# SCH__Umeko-DEC-H_htpa__2025-03-20_1.net
KiCad netlist of a schematic drawn in EasyEDA
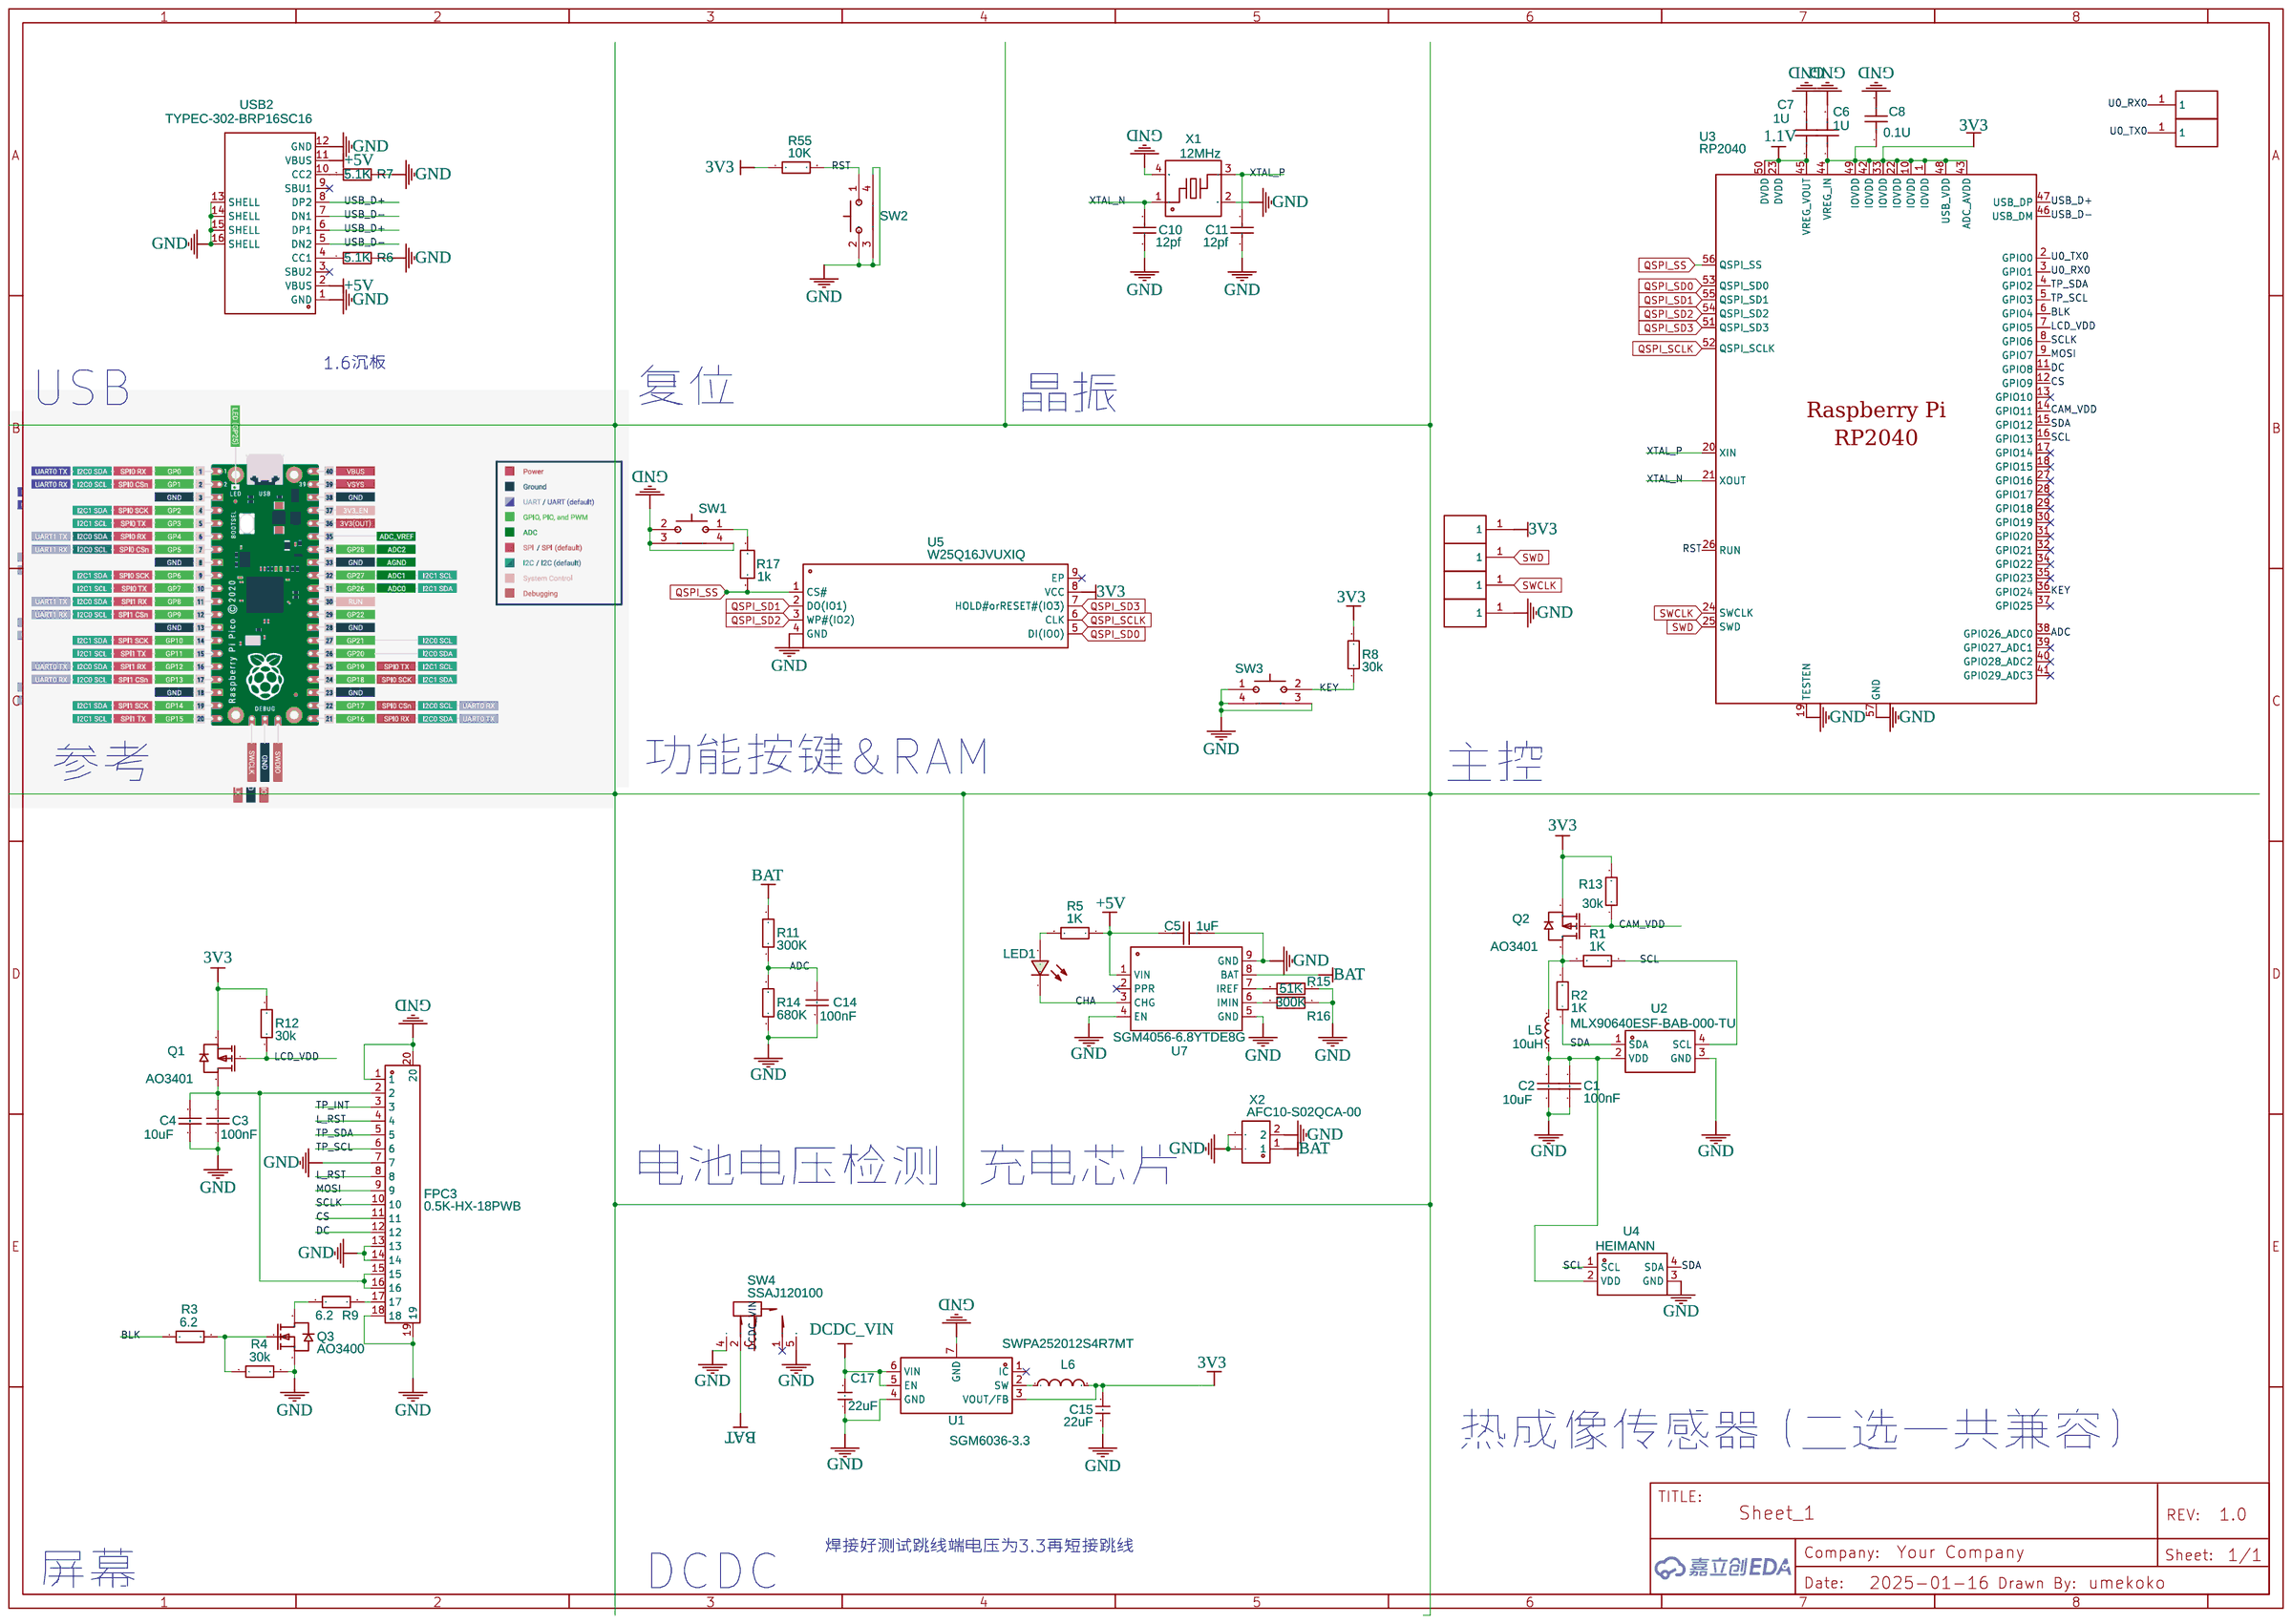
[diagram p0: schematic sheet]

(export (version "E")
  (design (tool "Eeschema 10.0.6"))
  (components
    (comp (ref "C1") (value "100nF") (libsource (lib "") (part "cap 0603_2")))
    (comp (ref "C2") (value "10uF") (libsource (lib "") (part "cap 0603")))
    (comp (ref "C3") (value "100nF") (libsource (lib "") (part "cap 0603")))
    (comp (ref "C4") (value "10uF") (libsource (lib "") (part "cap 0603")))
    (comp (ref "C5") (value "1uF") (libsource (lib "") (part "cap 0603_3")))
    (comp (ref "C6") (value "1U") (libsource (lib "") (part "C_0603_US")))
    (comp (ref "C7") (value "1U") (libsource (lib "") (part "C_0603_US")))
    (comp (ref "C8") (value "0.1U") (libsource (lib "") (part "C_0603_US")))
    (comp (ref "C10") (value "12pf") (libsource (lib "") (part "cap 0402")))
    (comp (ref "C11") (value "12pf") (libsource (lib "") (part "cap 0402_1")))
    (comp (ref "C14") (value "100nF") (libsource (lib "") (part "cap 0603")))
    (comp (ref "C15") (value "22uF") (libsource (lib "") (part "cap 0603_4")))
    (comp (ref "C17") (value "22uF") (libsource (lib "") (part "cap 0603_1")))
    (comp (ref "FPC3") (value "0.5K-HX-18PWB") (libsource (lib "") (part "0.5K-HX-18PWB")))
    (comp (ref "H1") (value "hp") (libsource (lib "") (part "hp")))
    (comp (ref "H2") (value "hp") (libsource (lib "") (part "hp")))
    (comp (ref "H3") (value "hp") (libsource (lib "") (part "hp_1")))
    (comp (ref "H4") (value "hp") (libsource (lib "") (part "hp_1")))
    (comp (ref "H5") (value "hp") (libsource (lib "") (part "hp_1")))
    (comp (ref "H6") (value "hp") (libsource (lib "") (part "hp_1")))
    (comp (ref "L5") (value "10uH") (libsource (lib "") (part "0805-L")))
    (comp (ref "L6") (value "SWPA252012S4R7MT") (libsource (lib "") (part "SWPA252012S2R2N")))
    (comp (ref "LED1") (value "led-0603") (libsource (lib "") (part "led-0603")))
    (comp (ref "Q1")
      (value "AO3401")
      (fields (field (name "Manufacturer") "IDCHIP(英锐芯)"))
      (libsource (lib "") (part "AO3401_C2848197"))
    )
    (comp (ref "Q2")
      (value "AO3401")
      (fields (field (name "Manufacturer") "IDCHIP(英锐芯)"))
      (libsource (lib "") (part "AO3401_C2848197"))
    )
    (comp (ref "Q3")
      (value "AO3400")
      (fields (field (name "Manufacturer") "IDCHIP(英锐芯)"))
      (libsource (lib "") (part "AO3400_C2848198"))
    )
    (comp (ref "R1") (value "1K") (libsource (lib "") (part "res-0603_2")))
    (comp (ref "R2") (value "1K") (libsource (lib "") (part "res-0603")))
    (comp (ref "R3") (value "6.2") (libsource (lib "") (part "res-0603_1")))
    (comp (ref "R4") (value "30k") (libsource (lib "") (part "res-0603_1")))
    (comp (ref "R5") (value "1K") (libsource (lib "") (part "res-0603_2")))
    (comp (ref "R6") (value "5.1K") (libsource (lib "") (part "res-0603_1")))
    (comp (ref "R7") (value "5.1K") (libsource (lib "") (part "res-0603_2")))
    (comp (ref "R8") (value "30k") (libsource (lib "") (part "res-0603")))
    (comp (ref "R9") (value "6.2") (libsource (lib "") (part "res-0603_1")))
    (comp (ref "R11") (value "300K") (libsource (lib "") (part "res-0603")))
    (comp (ref "R12") (value "30k") (libsource (lib "") (part "res-0603")))
    (comp (ref "R13") (value "30k") (libsource (lib "") (part "res-0603")))
    (comp (ref "R14") (value "680K") (libsource (lib "") (part "res-0603")))
    (comp (ref "R15") (value "51K") (libsource (lib "") (part "res-0603_2")))
    (comp (ref "R16") (value "300K") (libsource (lib "") (part "res-0603_2")))
    (comp (ref "R17") (value "1k") (libsource (lib "") (part "R_0603_EU")))
    (comp (ref "R55") (value "10K") (libsource (lib "") (part "res-0603_1")))
    (comp (ref "SW1") (value "1TS003B") (libsource (lib "") (part "1TS003B-1900-3500A_2")))
    (comp (ref "SW2") (value "1TS003B") (libsource (lib "") (part "1TS003B-1900-3500A_1")))
    (comp (ref "SW3") (value "1TS003B") (libsource (lib "") (part "1TS003B-1900-3500A")))
    (comp (ref "SW4")
      (value "SSAJ120100")
      (fields (field (name "Manufacturer") "ALPSALPINE(阿尔卑斯阿尔派)"))
      (libsource (lib "") (part "SSAJ120100"))
    )
    (comp (ref "U1") (value "SGM6036-3.3") (libsource (lib "") (part "SGM6036-ADJYUDT6G/TR")))
    (comp (ref "U2") (value "MLX90640ESF-BAB-000-TU") (libsource (lib "") (part "MLX90640ESF-BAB-000-TU_1")))
    (comp (ref "U3")
      (value "RP2040")
      (fields (field (name "Manufacturer") "Raspberry Pi(树莓派)"))
      (libsource (lib "") (part "RP2040"))
    )
    (comp (ref "U4") (value "HEIMANN") (libsource (lib "") (part "MLX90640ESF-BAB-000-TU")))
    (comp (ref "U5")
      (value "W25Q16JVUXIQ")
      (fields (field (name "Manufacturer") "WINBOND(华邦)"))
      (libsource (lib "") (part "W25Q16JVUXIQ"))
    )
    (comp (ref "U7") (value "SGM4056-6.8YTDE8G") (libsource (lib "") (part "SGM4056-6.8YTDE8G")))
    (comp (ref "USB2")
      (value "TYPEC-302-BRP16SC16")
      (fields (field (name "Manufacturer") "XUNPU(讯普)"))
      (libsource (lib "") (part "TYPEC-302-BRP16SC16"))
    )
    (comp (ref "X1") (value "12MHz") (libsource (lib "") (part "2016_4P")))
    (comp (ref "X2")
      (value "AFC10-S02QCA-00")
      (fields (field (name "Manufacturer") "JS(钜硕电子)"))
      (libsource (lib "") (part "AFC10-S02QCA-00"))
    )
  )
  (nets
    (net (code "1") (name "+5V") (class "Default")
      (node (ref "C5") (pin "1") (pinfunction "1_1") (pintype "unspecified"))
      (node (ref "R5") (pin "1") (pinfunction "1_1") (pintype "unspecified"))
      (node (ref "U7") (pin "1") (pinfunction "VIN_1") (pintype "unspecified"))
      (node (ref "USB2") (pin "11") (pinfunction "VBUS_11") (pintype "unspecified"))
      (node (ref "USB2") (pin "2") (pinfunction "VBUS_2") (pintype "unspecified"))
    )
    (net (code "2") (name "/ADC") (class "Default")
      (node (ref "C14") (pin "1") (pinfunction "1_1") (pintype "unspecified"))
      (node (ref "R11") (pin "1") (pinfunction "1_1") (pintype "unspecified"))
      (node (ref "R14") (pin "2") (pinfunction "2_2") (pintype "unspecified"))
      (node (ref "U3") (pin "38") (pinfunction "GPIO26_ADC0_38") (pintype "bidirectional"))
    )
    (net (code "3") (name "/BLK") (class "Default")
      (node (ref "R3") (pin "1") (pinfunction "1_1") (pintype "unspecified"))
      (node (ref "U3") (pin "6") (pinfunction "GPIO4_6") (pintype "bidirectional"))
    )
    (net (code "4") (name "/CAM_VDD") (class "Default")
      (node (ref "Q2") (pin "1") (pinfunction "G_1") (pintype "unspecified"))
      (node (ref "R13") (pin "1") (pinfunction "1_1") (pintype "unspecified"))
      (node (ref "U3") (pin "14") (pinfunction "GPIO11_14") (pintype "bidirectional"))
    )
    (net (code "5") (name "/CHA") (class "Default")
      (node (ref "LED1") (pin "1") (pinfunction "C_1") (pintype "input"))
      (node (ref "U7") (pin "3") (pinfunction "CHG_3") (pintype "unspecified"))
    )
    (net (code "6") (name "/CS") (class "Default")
      (node (ref "FPC3") (pin "11") (pinfunction "11_11") (pintype "unspecified"))
      (node (ref "U3") (pin "12") (pinfunction "GPIO9_12") (pintype "bidirectional"))
    )
    (net (code "7") (name "/DC") (class "Default")
      (node (ref "FPC3") (pin "12") (pinfunction "12_12") (pintype "unspecified"))
      (node (ref "U3") (pin "11") (pinfunction "GPIO8_11") (pintype "bidirectional"))
    )
    (net (code "8") (name "/KEY") (class "Default")
      (node (ref "R8") (pin "1") (pinfunction "1_1") (pintype "unspecified"))
      (node (ref "SW3") (pin "2") (pinfunction "2_2") (pintype "unspecified"))
      (node (ref "U3") (pin "36") (pinfunction "GPIO24_36") (pintype "bidirectional"))
    )
    (net (code "9") (name "/LCD_VDD") (class "Default")
      (node (ref "Q1") (pin "1") (pinfunction "G_1") (pintype "unspecified"))
      (node (ref "R12") (pin "1") (pinfunction "1_1") (pintype "unspecified"))
      (node (ref "U3") (pin "7") (pinfunction "GPIO5_7") (pintype "bidirectional"))
    )
    (net (code "10") (name "/L_RST") (class "Default")
      (node (ref "FPC3") (pin "4") (pinfunction "4_4") (pintype "unspecified"))
      (node (ref "FPC3") (pin "8") (pinfunction "8_8") (pintype "unspecified"))
    )
    (net (code "11") (name "/MOSI") (class "Default")
      (node (ref "FPC3") (pin "9") (pinfunction "9_9") (pintype "unspecified"))
      (node (ref "U3") (pin "9") (pinfunction "GPIO7_9") (pintype "bidirectional"))
    )
    (net (code "12") (name "/RST") (class "Default")
      (node (ref "R55") (pin "2") (pinfunction "2_2") (pintype "unspecified"))
      (node (ref "SW2") (pin "1") (pinfunction "1_1") (pintype "unspecified"))
      (node (ref "U3") (pin "26") (pinfunction "RUN_26") (pintype "input"))
    )
    (net (code "13") (name "/SCL") (class "Default")
      (node (ref "R1") (pin "1") (pinfunction "1_1") (pintype "unspecified"))
      (node (ref "U2") (pin "4") (pinfunction "SCL_4") (pintype "unspecified"))
      (node (ref "U3") (pin "16") (pinfunction "GPIO13_16") (pintype "bidirectional"))
      (node (ref "U4") (pin "1") (pinfunction "SCL_1") (pintype "unspecified"))
    )
    (net (code "14") (name "/SCLK") (class "Default")
      (node (ref "FPC3") (pin "10") (pinfunction "10_10") (pintype "unspecified"))
      (node (ref "U3") (pin "8") (pinfunction "GPIO6_8") (pintype "bidirectional"))
    )
    (net (code "15") (name "/SDA") (class "Default")
      (node (ref "R2") (pin "1") (pinfunction "1_1") (pintype "unspecified"))
      (node (ref "U2") (pin "1") (pinfunction "SDA_1") (pintype "unspecified"))
      (node (ref "U3") (pin "15") (pinfunction "GPIO12_15") (pintype "bidirectional"))
      (node (ref "U4") (pin "4") (pinfunction "SDA_4") (pintype "unspecified"))
    )
    (net (code "16") (name "/TP_INT") (class "Default")
      (node (ref "FPC3") (pin "3") (pinfunction "3_3") (pintype "unspecified"))
    )
    (net (code "17") (name "/TP_SCL") (class "Default")
      (node (ref "FPC3") (pin "6") (pinfunction "6_6") (pintype "unspecified"))
      (node (ref "U3") (pin "5") (pinfunction "GPIO3_5") (pintype "bidirectional"))
    )
    (net (code "18") (name "/TP_SDA") (class "Default")
      (node (ref "FPC3") (pin "5") (pinfunction "5_5") (pintype "unspecified"))
      (node (ref "U3") (pin "4") (pinfunction "GPIO2_4") (pintype "bidirectional"))
    )
    (net (code "19") (name "/U0_RX0") (class "Default")
      (node (ref "H1") (pin "1") (pinfunction "1_1") (pintype "unspecified"))
      (node (ref "U3") (pin "3") (pinfunction "GPIO1_3") (pintype "bidirectional"))
    )
    (net (code "20") (name "/U0_TX0") (class "Default")
      (node (ref "H2") (pin "1") (pinfunction "1_1") (pintype "unspecified"))
      (node (ref "U3") (pin "2") (pinfunction "GPIO0_2") (pintype "bidirectional"))
    )
    (net (code "21") (name "/USB_D+") (class "Default")
      (node (ref "U3") (pin "47") (pinfunction "USB_DP_47") (pintype "bidirectional"))
      (node (ref "USB2") (pin "6") (pinfunction "DP1_6") (pintype "unspecified"))
      (node (ref "USB2") (pin "8") (pinfunction "DP2_8") (pintype "unspecified"))
    )
    (net (code "22") (name "/USB_D-") (class "Default")
      (node (ref "U3") (pin "46") (pinfunction "USB_DM_46") (pintype "bidirectional"))
      (node (ref "USB2") (pin "5") (pinfunction "DN2_5") (pintype "unspecified"))
      (node (ref "USB2") (pin "7") (pinfunction "DN1_7") (pintype "unspecified"))
    )
    (net (code "23") (name "/XTAL_N") (class "Default")
      (node (ref "C10") (pin "1") (pinfunction "1_1") (pintype "input"))
      (node (ref "U3") (pin "21") (pinfunction "XOUT_21") (pintype "unspecified"))
      (node (ref "X1") (pin "1") (pinfunction "1_1") (pintype "input"))
    )
    (net (code "24") (name "/XTAL_P") (class "Default")
      (node (ref "C11") (pin "2") (pinfunction "2_2") (pintype "input"))
      (node (ref "U3") (pin "20") (pinfunction "XIN_20") (pintype "input"))
      (node (ref "X1") (pin "3") (pinfunction "3_3") (pintype "input"))
    )
    (net (code "25") (name "1.1V") (class "Default")
      (node (ref "C7") (pin "1") (pinfunction "1_1") (pintype "unspecified"))
      (node (ref "U3") (pin "23") (pinfunction "DVDD_23") (pintype "bidirectional"))
      (node (ref "U3") (pin "45") (pinfunction "VREG_VOUT_45") (pintype "bidirectional"))
      (node (ref "U3") (pin "50") (pinfunction "DVDD_50") (pintype "bidirectional"))
    )
    (net (code "26") (name "3V3") (class "Default")
      (node (ref "C15") (pin "2") (pinfunction "2_2") (pintype "unspecified"))
      (node (ref "C6") (pin "1") (pinfunction "1_1") (pintype "unspecified"))
      (node (ref "C8") (pin "1") (pinfunction "1_1") (pintype "unspecified"))
      (node (ref "H3") (pin "1") (pinfunction "1_1") (pintype "unspecified"))
      (node (ref "L6") (pin "2") (pinfunction "2_2") (pintype "unspecified"))
      (node (ref "Q1") (pin "2") (pinfunction "S_2") (pintype "unspecified"))
      (node (ref "Q2") (pin "2") (pinfunction "S_2") (pintype "unspecified"))
      (node (ref "R12") (pin "2") (pinfunction "2_2") (pintype "unspecified"))
      (node (ref "R13") (pin "2") (pinfunction "2_2") (pintype "unspecified"))
      (node (ref "R55") (pin "1") (pinfunction "1_1") (pintype "unspecified"))
      (node (ref "R8") (pin "2") (pinfunction "2_2") (pintype "unspecified"))
      (node (ref "U1") (pin "3") (pinfunction "VOUT/FB_3") (pintype "unspecified"))
      (node (ref "U3") (pin "1") (pinfunction "IOVDD_1") (pintype "bidirectional"))
      (node (ref "U3") (pin "10") (pinfunction "IOVDD_10") (pintype "bidirectional"))
      (node (ref "U3") (pin "22") (pinfunction "IOVDD_22") (pintype "bidirectional"))
      (node (ref "U3") (pin "33") (pinfunction "IOVDD_33") (pintype "bidirectional"))
      (node (ref "U3") (pin "42") (pinfunction "IOVDD_42") (pintype "bidirectional"))
      (node (ref "U3") (pin "43") (pinfunction "ADC_AVDD_43") (pintype "bidirectional"))
      (node (ref "U3") (pin "44") (pinfunction "VREG_IN_44") (pintype "bidirectional"))
      (node (ref "U3") (pin "48") (pinfunction "USB_VDD_48") (pintype "bidirectional"))
      (node (ref "U3") (pin "49") (pinfunction "IOVDD_49") (pintype "bidirectional"))
      (node (ref "U5") (pin "8") (pinfunction "VCC_8") (pintype "unspecified"))
    )
    (net (code "27") (name "BAT") (class "Default")
      (node (ref "R11") (pin "2") (pinfunction "2_2") (pintype "unspecified"))
      (node (ref "SW4") (pin "2") (pinfunction "2_2") (pintype "unspecified"))
      (node (ref "U7") (pin "8") (pinfunction "BAT_8") (pintype "unspecified"))
      (node (ref "X2") (pin "1") (pinfunction "1_1") (pintype "unspecified"))
    )
    (net (code "28") (name "DCDC_VIN") (class "Default")
      (node (ref "C17") (pin "2") (pinfunction "2_2") (pintype "unspecified"))
      (node (ref "SW4") (pin "C") (pinfunction "C_C") (pintype "unspecified"))
      (node (ref "U1") (pin "5") (pinfunction "EN_5") (pintype "unspecified"))
      (node (ref "U1") (pin "6") (pinfunction "VIN_6") (pintype "unspecified"))
    )
    (net (code "29") (name "GND") (class "Default")
      (node (ref "C1") (pin "2") (pinfunction "2_2") (pintype "unspecified"))
      (node (ref "C10") (pin "2") (pinfunction "2_2") (pintype "input"))
      (node (ref "C11") (pin "1") (pinfunction "1_1") (pintype "input"))
      (node (ref "C14") (pin "2") (pinfunction "2_2") (pintype "unspecified"))
      (node (ref "C15") (pin "1") (pinfunction "1_1") (pintype "unspecified"))
      (node (ref "C17") (pin "1") (pinfunction "1_1") (pintype "unspecified"))
      (node (ref "C2") (pin "2") (pinfunction "2_2") (pintype "unspecified"))
      (node (ref "C3") (pin "2") (pinfunction "2_2") (pintype "unspecified"))
      (node (ref "C4") (pin "2") (pinfunction "2_2") (pintype "unspecified"))
      (node (ref "C5") (pin "2") (pinfunction "2_2") (pintype "unspecified"))
      (node (ref "C6") (pin "2") (pinfunction "2_2") (pintype "unspecified"))
      (node (ref "C7") (pin "2") (pinfunction "2_2") (pintype "unspecified"))
      (node (ref "C8") (pin "2") (pinfunction "2_2") (pintype "unspecified"))
      (node (ref "FPC3") (pin "1") (pinfunction "1_1") (pintype "unspecified"))
      (node (ref "FPC3") (pin "13") (pinfunction "13_13") (pintype "unspecified"))
      (node (ref "FPC3") (pin "14") (pinfunction "14_14") (pintype "unspecified"))
      (node (ref "FPC3") (pin "18") (pinfunction "18_18") (pintype "unspecified"))
      (node (ref "FPC3") (pin "19") (pinfunction "19_19") (pintype "unspecified"))
      (node (ref "FPC3") (pin "20") (pinfunction "20_20") (pintype "unspecified"))
      (node (ref "FPC3") (pin "7") (pinfunction "7_7") (pintype "unspecified"))
      (node (ref "H4") (pin "1") (pinfunction "1_1") (pintype "unspecified"))
      (node (ref "Q3") (pin "2") (pinfunction "S_2") (pintype "unspecified"))
      (node (ref "R14") (pin "1") (pinfunction "1_1") (pintype "unspecified"))
      (node (ref "R15") (pin "1") (pinfunction "1_1") (pintype "unspecified"))
      (node (ref "R16") (pin "1") (pinfunction "1_1") (pintype "unspecified"))
      (node (ref "R4") (pin "2") (pinfunction "2_2") (pintype "unspecified"))
      (node (ref "R6") (pin "2") (pinfunction "2_2") (pintype "unspecified"))
      (node (ref "R7") (pin "1") (pinfunction "1_1") (pintype "unspecified"))
      (node (ref "SW1") (pin "2") (pinfunction "2_2") (pintype "unspecified"))
      (node (ref "SW1") (pin "3") (pinfunction "3_3") (pintype "unspecified"))
      (node (ref "SW1") (pin "4") (pinfunction "4_4") (pintype "unspecified"))
      (node (ref "SW2") (pin "2") (pinfunction "2_2") (pintype "unspecified"))
      (node (ref "SW2") (pin "3") (pinfunction "3_3") (pintype "unspecified"))
      (node (ref "SW2") (pin "4") (pinfunction "4_4") (pintype "unspecified"))
      (node (ref "SW3") (pin "1") (pinfunction "1_1") (pintype "unspecified"))
      (node (ref "SW3") (pin "3") (pinfunction "3_3") (pintype "unspecified"))
      (node (ref "SW3") (pin "4") (pinfunction "4_4") (pintype "unspecified"))
      (node (ref "SW4") (pin "4") (pinfunction "4_4") (pintype "unspecified"))
      (node (ref "SW4") (pin "5") (pinfunction "5_5") (pintype "unspecified"))
      (node (ref "U1") (pin "4") (pinfunction "GND_4") (pintype "unspecified"))
      (node (ref "U1") (pin "7") (pinfunction "GND_7") (pintype "unspecified"))
      (node (ref "U2") (pin "3") (pinfunction "GND_3") (pintype "unspecified"))
      (node (ref "U3") (pin "19") (pinfunction "TESTEN_19") (pintype "unspecified"))
      (node (ref "U3") (pin "57") (pinfunction "GND_57") (pintype "bidirectional"))
      (node (ref "U4") (pin "3") (pinfunction "GND_3") (pintype "unspecified"))
      (node (ref "U5") (pin "4") (pinfunction "GND_4") (pintype "unspecified"))
      (node (ref "U7") (pin "4") (pinfunction "EN_4") (pintype "unspecified"))
      (node (ref "U7") (pin "5") (pinfunction "GND_5") (pintype "unspecified"))
      (node (ref "U7") (pin "9") (pinfunction "GND_9") (pintype "unspecified"))
      (node (ref "USB2") (pin "1") (pinfunction "GND_1") (pintype "unspecified"))
      (node (ref "USB2") (pin "12") (pinfunction "GND_12") (pintype "unspecified"))
      (node (ref "USB2") (pin "13") (pinfunction "SHELL_13") (pintype "unspecified"))
      (node (ref "USB2") (pin "14") (pinfunction "SHELL_14") (pintype "unspecified"))
      (node (ref "USB2") (pin "15") (pinfunction "SHELL_15") (pintype "unspecified"))
      (node (ref "USB2") (pin "16") (pinfunction "SHELL_16") (pintype "unspecified"))
      (node (ref "X1") (pin "2") (pinfunction "GND_2") (pintype "input"))
      (node (ref "X1") (pin "4") (pinfunction "GND_4") (pintype "input"))
      (node (ref "X2") (pin "2") (pinfunction "2_2") (pintype "unspecified"))
      (node (ref "X2") (pin "3") (pinfunction "3_3") (pintype "unspecified"))
      (node (ref "X2") (pin "4") (pinfunction "4_4") (pintype "unspecified"))
    )
    (net (code "30") (name "Net-(FPC3-Pad17)") (class "Default")
      (node (ref "FPC3") (pin "17") (pinfunction "17_17") (pintype "unspecified"))
      (node (ref "R9") (pin "2") (pinfunction "2_2") (pintype "unspecified"))
    )
    (net (code "31") (name "Net-(LED1-A)") (class "Default")
      (node (ref "LED1") (pin "2") (pinfunction "A_2") (pintype "input"))
      (node (ref "R5") (pin "2") (pinfunction "2_2") (pintype "unspecified"))
    )
    (net (code "32") (name "Net-(Q1-D)") (class "Default")
      (node (ref "C3") (pin "1") (pinfunction "1_1") (pintype "unspecified"))
      (node (ref "C4") (pin "1") (pinfunction "1_1") (pintype "unspecified"))
      (node (ref "FPC3") (pin "15") (pinfunction "15_15") (pintype "unspecified"))
      (node (ref "FPC3") (pin "16") (pinfunction "16_16") (pintype "unspecified"))
      (node (ref "FPC3") (pin "2") (pinfunction "2_2") (pintype "unspecified"))
      (node (ref "Q1") (pin "3") (pinfunction "D_3") (pintype "unspecified"))
    )
    (net (code "33") (name "Net-(Q2-D)") (class "Default")
      (node (ref "L5") (pin "2") (pinfunction "2_2") (pintype "unspecified"))
      (node (ref "Q2") (pin "3") (pinfunction "D_3") (pintype "unspecified"))
      (node (ref "R1") (pin "2") (pinfunction "2_2") (pintype "unspecified"))
      (node (ref "R2") (pin "2") (pinfunction "2_2") (pintype "unspecified"))
    )
    (net (code "34") (name "Net-(Q3-D)") (class "Default")
      (node (ref "Q3") (pin "3") (pinfunction "D_3") (pintype "unspecified"))
      (node (ref "R9") (pin "1") (pinfunction "1_1") (pintype "unspecified"))
    )
    (net (code "35") (name "Net-(Q3-G)") (class "Default")
      (node (ref "Q3") (pin "1") (pinfunction "G_1") (pintype "unspecified"))
      (node (ref "R3") (pin "2") (pinfunction "2_2") (pintype "unspecified"))
      (node (ref "R4") (pin "1") (pinfunction "1_1") (pintype "unspecified"))
    )
    (net (code "36") (name "Net-(R17-Pad2)") (class "Default")
      (node (ref "R17") (pin "2") (pinfunction "2_2") (pintype "unspecified"))
      (node (ref "SW1") (pin "1") (pinfunction "1_1") (pintype "unspecified"))
    )
    (net (code "37") (name "Net-(U1-SW)") (class "Default")
      (node (ref "L6") (pin "1") (pinfunction "1_1") (pintype "unspecified"))
      (node (ref "U1") (pin "2") (pinfunction "SW_2") (pintype "unspecified"))
    )
    (net (code "38") (name "Net-(U2-VDD)") (class "Default")
      (node (ref "C1") (pin "1") (pinfunction "1_1") (pintype "unspecified"))
      (node (ref "C2") (pin "1") (pinfunction "1_1") (pintype "unspecified"))
      (node (ref "L5") (pin "1") (pinfunction "1_1") (pintype "unspecified"))
      (node (ref "U2") (pin "2") (pinfunction "VDD_2") (pintype "unspecified"))
      (node (ref "U4") (pin "2") (pinfunction "VDD_2") (pintype "unspecified"))
    )
    (net (code "39") (name "Net-(U7-IMIN)") (class "Default")
      (node (ref "R16") (pin "2") (pinfunction "2_2") (pintype "unspecified"))
      (node (ref "U7") (pin "6") (pinfunction "IMIN_6") (pintype "unspecified"))
    )
    (net (code "40") (name "Net-(U7-IREF)") (class "Default")
      (node (ref "R15") (pin "2") (pinfunction "2_2") (pintype "unspecified"))
      (node (ref "U7") (pin "7") (pinfunction "IREF_7") (pintype "unspecified"))
    )
    (net (code "41") (name "Net-(USB2-CC1)") (class "Default")
      (node (ref "R6") (pin "1") (pinfunction "1_1") (pintype "unspecified"))
      (node (ref "USB2") (pin "4") (pinfunction "CC1_4") (pintype "unspecified"))
    )
    (net (code "42") (name "Net-(USB2-CC2)") (class "Default")
      (node (ref "R7") (pin "2") (pinfunction "2_2") (pintype "unspecified"))
      (node (ref "USB2") (pin "10") (pinfunction "CC2_10") (pintype "unspecified"))
    )
    (net (code "43") (name "QSPI_SCLK") (class "Default")
      (node (ref "U3") (pin "52") (pinfunction "QSPI_SCLK_52") (pintype "output"))
      (node (ref "U5") (pin "6") (pinfunction "CLK_6") (pintype "unspecified"))
    )
    (net (code "44") (name "QSPI_SD0") (class "Default")
      (node (ref "U3") (pin "53") (pinfunction "QSPI_SD0_53") (pintype "bidirectional"))
      (node (ref "U5") (pin "5") (pinfunction "DI(IO0)_5") (pintype "unspecified"))
    )
    (net (code "45") (name "QSPI_SD1") (class "Default")
      (node (ref "U3") (pin "55") (pinfunction "QSPI_SD1_55") (pintype "bidirectional"))
      (node (ref "U5") (pin "2") (pinfunction "DO(IO1)_2") (pintype "unspecified"))
    )
    (net (code "46") (name "QSPI_SD2") (class "Default")
      (node (ref "U3") (pin "54") (pinfunction "QSPI_SD2_54") (pintype "bidirectional"))
      (node (ref "U5") (pin "3") (pinfunction "WP#(IO2)_3") (pintype "unspecified"))
    )
    (net (code "47") (name "QSPI_SD3") (class "Default")
      (node (ref "U3") (pin "51") (pinfunction "QSPI_SD3_51") (pintype "bidirectional"))
      (node (ref "U5") (pin "7") (pinfunction "HOLD#orRESET#(IO3)_7") (pintype "unspecified"))
    )
    (net (code "48") (name "QSPI_SS") (class "Default")
      (node (ref "R17") (pin "1") (pinfunction "1_1") (pintype "unspecified"))
      (node (ref "U3") (pin "56") (pinfunction "QSPI_SS_56") (pintype "bidirectional"))
      (node (ref "U5") (pin "1") (pinfunction "CS#_1") (pintype "unspecified"))
    )
    (net (code "49") (name "SWCLK") (class "Default")
      (node (ref "H6") (pin "1") (pinfunction "1_1") (pintype "unspecified"))
      (node (ref "U3") (pin "24") (pinfunction "SWCLK_24") (pintype "output"))
    )
    (net (code "50") (name "SWD") (class "Default")
      (node (ref "H5") (pin "1") (pinfunction "1_1") (pintype "unspecified"))
      (node (ref "U3") (pin "25") (pinfunction "SWD_25") (pintype "bidirectional"))
    )
    (net (code "51") (name "unconnected-(SW4-Pad1)") (class "Default")
      (node (ref "SW4") (pin "1") (pinfunction "1_1") (pintype "unspecified+no_connect"))
    )
    (net (code "52") (name "unconnected-(U1-IC-Pad1)") (class "Default")
      (node (ref "U1") (pin "1") (pinfunction "IC_1") (pintype "unspecified+no_connect"))
    )
    (net (code "53") (name "unconnected-(U3-GPIO10-Pad13)") (class "Default")
      (node (ref "U3") (pin "13") (pinfunction "GPIO10_13") (pintype "bidirectional+no_connect"))
    )
    (net (code "54") (name "unconnected-(U3-GPIO14-Pad17)") (class "Default")
      (node (ref "U3") (pin "17") (pinfunction "GPIO14_17") (pintype "bidirectional+no_connect"))
    )
    (net (code "55") (name "unconnected-(U3-GPIO15-Pad18)") (class "Default")
      (node (ref "U3") (pin "18") (pinfunction "GPIO15_18") (pintype "bidirectional+no_connect"))
    )
    (net (code "56") (name "unconnected-(U3-GPIO16-Pad27)") (class "Default")
      (node (ref "U3") (pin "27") (pinfunction "GPIO16_27") (pintype "bidirectional+no_connect"))
    )
    (net (code "57") (name "unconnected-(U3-GPIO17-Pad28)") (class "Default")
      (node (ref "U3") (pin "28") (pinfunction "GPIO17_28") (pintype "bidirectional+no_connect"))
    )
    (net (code "58") (name "unconnected-(U3-GPIO18-Pad29)") (class "Default")
      (node (ref "U3") (pin "29") (pinfunction "GPIO18_29") (pintype "bidirectional+no_connect"))
    )
    (net (code "59") (name "unconnected-(U3-GPIO19-Pad30)") (class "Default")
      (node (ref "U3") (pin "30") (pinfunction "GPIO19_30") (pintype "bidirectional+no_connect"))
    )
    (net (code "60") (name "unconnected-(U3-GPIO20-Pad31)") (class "Default")
      (node (ref "U3") (pin "31") (pinfunction "GPIO20_31") (pintype "bidirectional+no_connect"))
    )
    (net (code "61") (name "unconnected-(U3-GPIO21-Pad32)") (class "Default")
      (node (ref "U3") (pin "32") (pinfunction "GPIO21_32") (pintype "bidirectional+no_connect"))
    )
    (net (code "62") (name "unconnected-(U3-GPIO22-Pad34)") (class "Default")
      (node (ref "U3") (pin "34") (pinfunction "GPIO22_34") (pintype "bidirectional+no_connect"))
    )
    (net (code "63") (name "unconnected-(U3-GPIO23-Pad35)") (class "Default")
      (node (ref "U3") (pin "35") (pinfunction "GPIO23_35") (pintype "bidirectional+no_connect"))
    )
    (net (code "64") (name "unconnected-(U3-GPIO25-Pad37)") (class "Default")
      (node (ref "U3") (pin "37") (pinfunction "GPIO25_37") (pintype "bidirectional+no_connect"))
    )
    (net (code "65") (name "unconnected-(U3-GPIO27_ADC1-Pad39)") (class "Default")
      (node (ref "U3") (pin "39") (pinfunction "GPIO27_ADC1_39") (pintype "bidirectional+no_connect"))
    )
    (net (code "66") (name "unconnected-(U3-GPIO28_ADC2-Pad40)") (class "Default")
      (node (ref "U3") (pin "40") (pinfunction "GPIO28_ADC2_40") (pintype "bidirectional+no_connect"))
    )
    (net (code "67") (name "unconnected-(U3-GPIO29_ADC3-Pad41)") (class "Default")
      (node (ref "U3") (pin "41") (pinfunction "GPIO29_ADC3_41") (pintype "bidirectional+no_connect"))
    )
    (net (code "68") (name "unconnected-(U5-EP-Pad9)") (class "Default")
      (node (ref "U5") (pin "9") (pinfunction "EP_9") (pintype "unspecified+no_connect"))
    )
    (net (code "69") (name "unconnected-(U7-PPR-Pad2)") (class "Default")
      (node (ref "U7") (pin "2") (pinfunction "PPR_2") (pintype "unspecified"))
    )
    (net (code "70") (name "unconnected-(USB2-SBU1-Pad9)") (class "Default")
      (node (ref "USB2") (pin "9") (pinfunction "SBU1_9") (pintype "unspecified+no_connect"))
    )
    (net (code "71") (name "unconnected-(USB2-SBU2-Pad3)") (class "Default")
      (node (ref "USB2") (pin "3") (pinfunction "SBU2_3") (pintype "unspecified+no_connect"))
    )
  )
)
